# Connector.net
KiCad netlist of a schematic drawn in Altium Designer
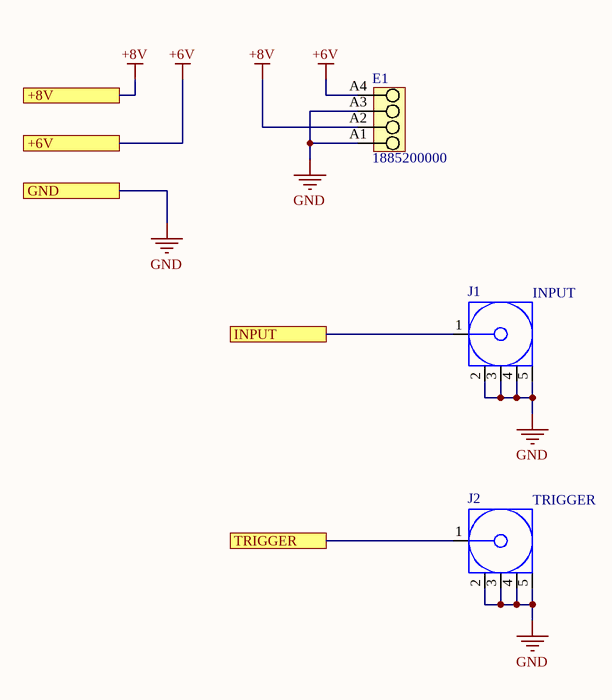
[diagram p0: Connector.SchDoc]

(export (version "E")
  (design (tool "Eeschema 10.0.6"))
  (components
    (comp (ref "E1")
      (value "1885200000")
      (footprint "LSF_SMT_3_5_135_04")
      (description "OMNIMATE Signal - series LSF")
      (fields (field (name "MANUFACTURER") "Weidmueller"))
      (libsource (lib "Altium Content Vault") (part "Terminal_04_1x04"))
    )
    (comp (ref "J1")
      (value "INPUT")
      (footprint "MOLX-731000114_V")
      (description "SMA Right-Angle PCB Jack Receptacle, Brass Body, Gold Plated, 50 Ohm, 5-Pin THD, RoHS, Tray")
      (fields (field (name "MANUFACTURER") "Molex"))
      (libsource (lib "Altium Content Vault") (part "CN-S-4F-RF5"))
    )
    (comp (ref "J2")
      (value "TRIGGER")
      (footprint "MOLX-731000114_V")
      (description "SMA Right-Angle PCB Jack Receptacle, Brass Body, Gold Plated, 50 Ohm, 5-Pin THD, RoHS, Tray")
      (fields (field (name "MANUFACTURER") "Molex"))
      (libsource (lib "Altium Content Vault") (part "CN-S-4F-RF5"))
    )
  )
  (nets
    (net (code "1") (name "+6V") (class "Default")
      (node (ref "E1") (pin "A4") (pinfunction "A4_A4") (pintype "passive"))
    )
    (net (code "2") (name "+8V") (class "Default")
      (node (ref "E1") (pin "A2") (pinfunction "A2_A2") (pintype "passive"))
    )
    (net (code "3") (name "/INPUT") (class "Default")
      (node (ref "J1") (pin "1") (pinfunction "1_1") (pintype "passive"))
    )
    (net (code "4") (name "/TRIGGER") (class "Default")
      (node (ref "J2") (pin "1") (pinfunction "1_1") (pintype "passive"))
    )
    (net (code "5") (name "GND") (class "Default")
      (node (ref "E1") (pin "A1") (pinfunction "A1_A1") (pintype "passive"))
      (node (ref "E1") (pin "A3") (pinfunction "A3_A3") (pintype "passive"))
      (node (ref "J1") (pin "2") (pinfunction "2_2") (pintype "passive"))
      (node (ref "J1") (pin "3") (pinfunction "3_3") (pintype "passive"))
      (node (ref "J1") (pin "4") (pinfunction "4_4") (pintype "passive"))
      (node (ref "J1") (pin "5") (pinfunction "5_5") (pintype "passive"))
      (node (ref "J2") (pin "2") (pinfunction "2_2") (pintype "passive"))
      (node (ref "J2") (pin "3") (pinfunction "3_3") (pintype "passive"))
      (node (ref "J2") (pin "4") (pinfunction "4_4") (pintype "passive"))
      (node (ref "J2") (pin "5") (pinfunction "5_5") (pintype "passive"))
    )
  )
)
